# PCF8574.net
KiCad netlist of a schematic drawn in Altium Designer
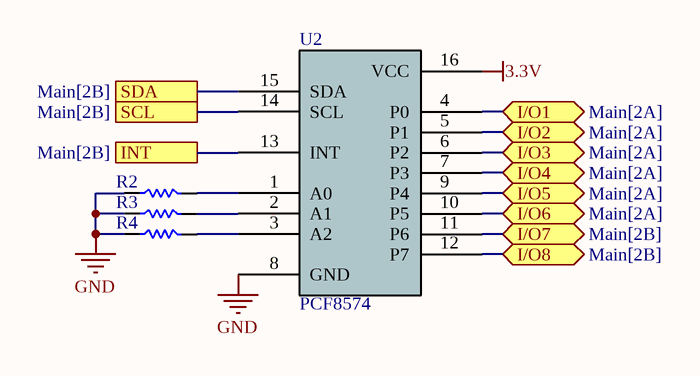
[diagram p0: PCF8574.SchDoc]

(export (version "E")
  (design (tool "Eeschema 10.0.6"))
  (components
    (comp (ref "R2")
      (value "10K")
      (footprint "R 0805")
      (description "Chip resistor")
      (fields (field (name "版权归属") "源创客"))
      (libsource (lib "Passive (Resistor-Capacitor-Inductor-Veristor-Ferrite)") (part "R"))
    )
    (comp (ref "R3")
      (value "10K")
      (footprint "R 0805")
      (description "Chip resistor")
      (fields (field (name "版权归属") "源创客"))
      (libsource (lib "Passive (Resistor-Capacitor-Inductor-Veristor-Ferrite)") (part "R"))
    )
    (comp (ref "R4")
      (value "10K")
      (footprint "R 0805")
      (description "Chip resistor")
      (fields (field (name "版权归属") "源创客"))
      (libsource (lib "Passive (Resistor-Capacitor-Inductor-Veristor-Ferrite)") (part "R"))
    )
    (comp (ref "U2")
      (value "PCF8574")
      (footprint "SOP16W_M")
      (description "Remote 8-Bit I/O Expander for I  2C Bus")
      (libsource (lib "Integrated Circuit") (part "PCF8574"))
    )
  )
  (nets
    (net (code "1") (name "/INT") (class "Default")
      (node (ref "U2") (pin "13") (pinfunction "INT_13") (pintype "passive"))
    )
    (net (code "2") (name "/I{slash}O1") (class "Default")
      (node (ref "U2") (pin "4") (pinfunction "P0_4") (pintype "passive"))
    )
    (net (code "3") (name "/I{slash}O2") (class "Default")
      (node (ref "U2") (pin "5") (pinfunction "P1_5") (pintype "passive"))
    )
    (net (code "4") (name "/I{slash}O3") (class "Default")
      (node (ref "U2") (pin "6") (pinfunction "P2_6") (pintype "passive"))
    )
    (net (code "5") (name "/I{slash}O4") (class "Default")
      (node (ref "U2") (pin "7") (pinfunction "P3_7") (pintype "passive"))
    )
    (net (code "6") (name "/I{slash}O5") (class "Default")
      (node (ref "U2") (pin "9") (pinfunction "P4_9") (pintype "passive"))
    )
    (net (code "7") (name "/I{slash}O6") (class "Default")
      (node (ref "U2") (pin "10") (pinfunction "P5_10") (pintype "passive"))
    )
    (net (code "8") (name "/I{slash}O7") (class "Default")
      (node (ref "U2") (pin "11") (pinfunction "P6_11") (pintype "passive"))
    )
    (net (code "9") (name "/I{slash}O8") (class "Default")
      (node (ref "U2") (pin "12") (pinfunction "P7_12") (pintype "passive"))
    )
    (net (code "10") (name "/SCL") (class "Default")
      (node (ref "U2") (pin "14") (pinfunction "SCL_14") (pintype "passive"))
    )
    (net (code "11") (name "/SDA") (class "Default")
      (node (ref "U2") (pin "15") (pinfunction "SDA_15") (pintype "passive"))
    )
    (net (code "12") (name "3.3V") (class "Default")
      (node (ref "U2") (pin "16") (pinfunction "VCC_16") (pintype "passive"))
    )
    (net (code "13") (name "GND") (class "Default")
      (node (ref "R2") (pin "1") (pinfunction "1_1") (pintype "passive"))
      (node (ref "R3") (pin "1") (pinfunction "1_1") (pintype "passive"))
      (node (ref "R4") (pin "1") (pinfunction "1_1") (pintype "passive"))
      (node (ref "U2") (pin "8") (pinfunction "GND_8") (pintype "passive"))
    )
    (net (code "14") (name "Net-(U2-A0)") (class "Default")
      (node (ref "R2") (pin "2") (pinfunction "2_2") (pintype "passive"))
      (node (ref "U2") (pin "1") (pinfunction "A0_1") (pintype "passive"))
    )
    (net (code "15") (name "Net-(U2-A1)") (class "Default")
      (node (ref "R3") (pin "2") (pinfunction "2_2") (pintype "passive"))
      (node (ref "U2") (pin "2") (pinfunction "A1_2") (pintype "passive"))
    )
    (net (code "16") (name "Net-(U2-A2)") (class "Default")
      (node (ref "R4") (pin "2") (pinfunction "2_2") (pintype "passive"))
      (node (ref "U2") (pin "3") (pinfunction "A2_3") (pintype "passive"))
    )
  )
)
